# 3V8_Buck_Boost_Converter.net
KiCad netlist of a schematic drawn in Altium Designer
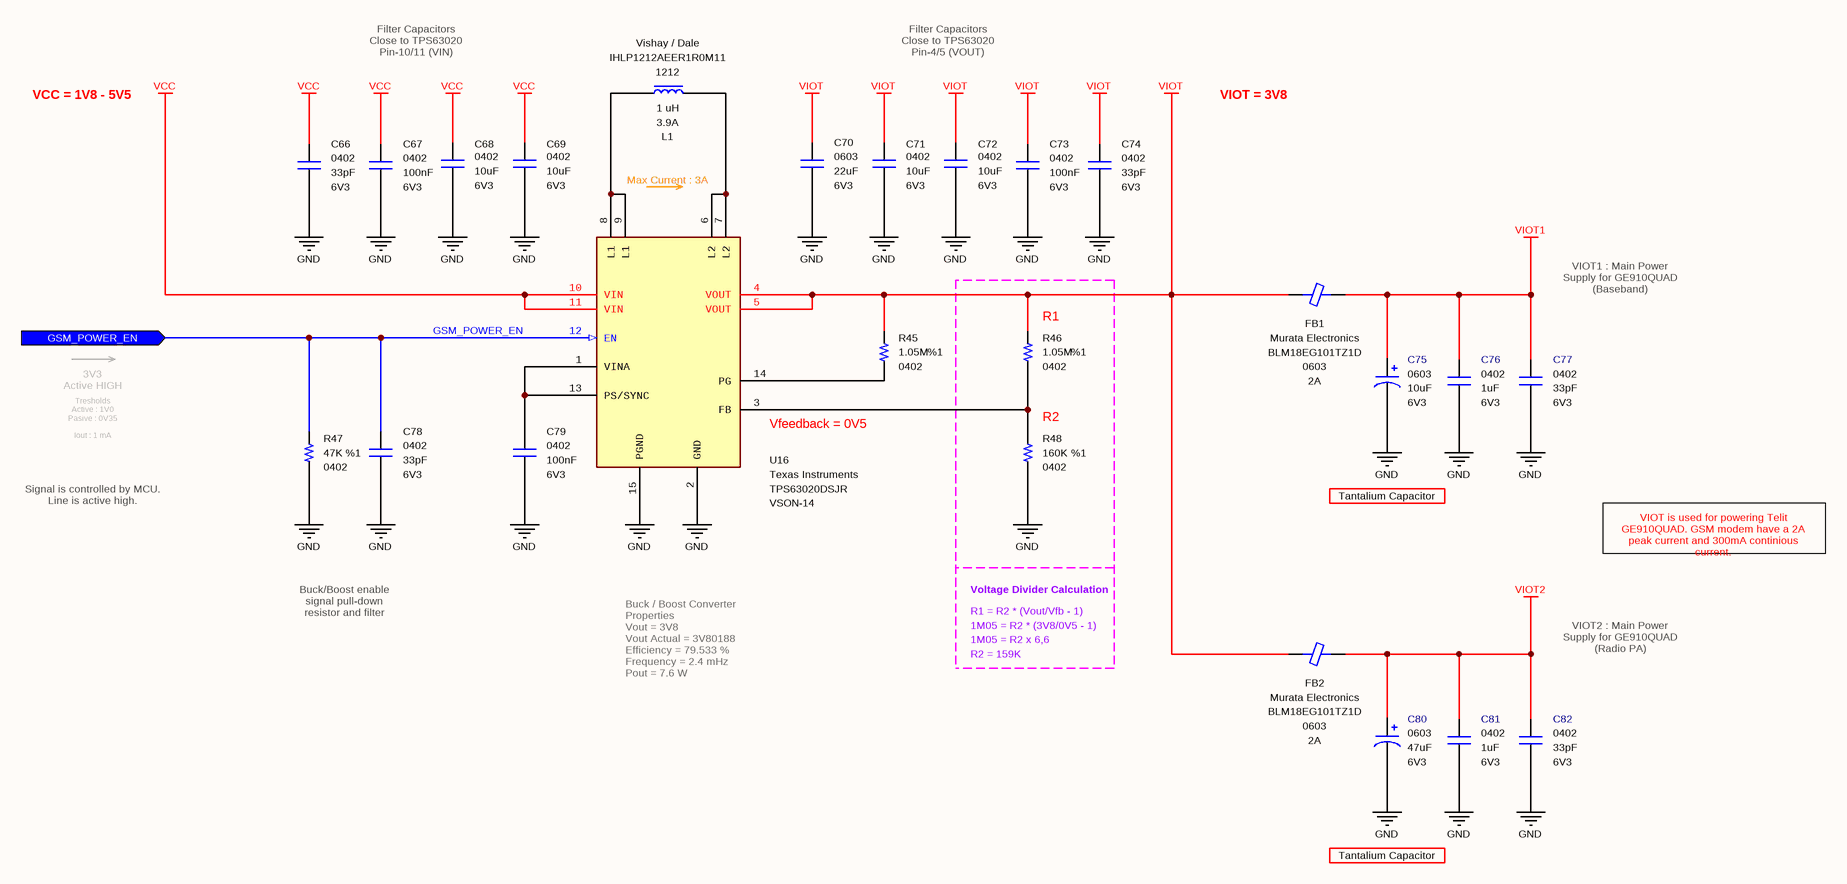
[diagram p0: 3V8 Buck Boost Converter.SchDoc]

(export (version "E")
  (design (tool "Eeschema 10.0.6"))
  (components
    (comp (ref "C66")
      (value "33pF")
      (footprint "CAPACITOR_0402")
      (description "Capacitor - 33pF [0402] (Ceramic)")
      (fields
        (field (name "TOLERANCE") "10%")
        (field (name "CASE") "0402")
        (field (name "VOLTAGE") "6V3")
        (field (name "MANUFACTURER PART NUMBER") "C0402C330J9RACAUTO")
      )
      (libsource (lib "Ovoo_Library") (part "Capacitor - 33pF [0402-6V3]"))
    )
    (comp (ref "C67")
      (value "100nF")
      (footprint "CAPACITOR_0402")
      (description "Capacitor - 100nF [0402-6V3] (Ceramic)")
      (fields
        (field (name "CASE") "0402")
        (field (name "TOLERANCE") "%10")
        (field (name "VOLTAGE") "6V3")
        (field (name "MANUFACTURER PART NUMBER") "04026D104KAT4A")
      )
      (libsource (lib "Ovoo_Library") (part "Capacitor - 100nF [0402-6V3]"))
    )
    (comp (ref "C68")
      (value "10uF")
      (footprint "CAPACITOR_0402")
      (description "Capacitor - 10uF [0402] (Ceramic)")
      (fields
        (field (name "MANUFACTURER PART NUMBER") "C0402C106M9PACTU")
        (field (name "MOUSER PART NUMBER") "80-C0402C106M9P")
        (field (name "CASE") "0402")
        (field (name "VOLTAGE") "6V3")
      )
      (libsource (lib "Ovoo_Library") (part "Capacitor - 10uF [0402-6V3]"))
    )
    (comp (ref "C69")
      (value "10uF")
      (footprint "CAPACITOR_0402")
      (description "Capacitor - 10uF [0402] (Ceramic)")
      (fields
        (field (name "MANUFACTURER PART NUMBER") "C0402C106M9PACTU")
        (field (name "MOUSER PART NUMBER") "80-C0402C106M9P")
        (field (name "CASE") "0402")
        (field (name "VOLTAGE") "6V3")
      )
      (libsource (lib "Ovoo_Library") (part "Capacitor - 10uF [0402-6V3]"))
    )
    (comp (ref "C70")
      (value "22uF")
      (footprint "CAPACITOR_0603")
      (description "Capacitor - 22uF [0603] (Ceramic)")
      (fields
        (field (name "MANUFACTURER PART NUMBER") "GRM188R60J226MEA0D")
        (field (name "TOLERANCE") "%20")
        (field (name "CASE") "0603")
        (field (name "VOLTAGE") "6V3")
      )
      (libsource (lib "Ovoo_Library") (part "Capacitor - 22uF [0603-6V3]"))
    )
    (comp (ref "C71")
      (value "10uF")
      (footprint "CAPACITOR_0402")
      (description "Capacitor - 10uF [0402] (Ceramic)")
      (fields
        (field (name "MANUFACTURER PART NUMBER") "C0402C106M9PACTU")
        (field (name "MOUSER PART NUMBER") "80-C0402C106M9P")
        (field (name "CASE") "0402")
        (field (name "VOLTAGE") "6V3")
      )
      (libsource (lib "Ovoo_Library") (part "Capacitor - 10uF [0402-6V3]"))
    )
    (comp (ref "C72")
      (value "10uF")
      (footprint "CAPACITOR_0402")
      (description "Capacitor - 10uF [0402] (Ceramic)")
      (fields
        (field (name "MANUFACTURER PART NUMBER") "C0402C106M9PACTU")
        (field (name "MOUSER PART NUMBER") "80-C0402C106M9P")
        (field (name "CASE") "0402")
        (field (name "VOLTAGE") "6V3")
      )
      (libsource (lib "Ovoo_Library") (part "Capacitor - 10uF [0402-6V3]"))
    )
    (comp (ref "C73")
      (value "100nF")
      (footprint "CAPACITOR_0402")
      (description "Capacitor - 100nF [0402-6V3] (Ceramic)")
      (fields
        (field (name "CASE") "0402")
        (field (name "TOLERANCE") "%10")
        (field (name "VOLTAGE") "6V3")
        (field (name "MANUFACTURER PART NUMBER") "04026D104KAT4A")
      )
      (libsource (lib "Ovoo_Library") (part "Capacitor - 100nF [0402-6V3]"))
    )
    (comp (ref "C74")
      (value "33pF")
      (footprint "CAPACITOR_0402")
      (description "Capacitor - 33pF [0402] (Ceramic)")
      (fields
        (field (name "TOLERANCE") "10%")
        (field (name "CASE") "0402")
        (field (name "VOLTAGE") "6V3")
        (field (name "MANUFACTURER PART NUMBER") "C0402C330J9RACAUTO")
      )
      (libsource (lib "Ovoo_Library") (part "Capacitor - 33pF [0402-6V3]"))
    )
    (comp (ref "C75")
      (value "10uF")
      (footprint "CAPACITOR_0603 - TANTALUM")
      (description "Capacitor - 10uF [0603] (Tantalium)")
      (fields
        (field (name "TOLERANCE") "20%")
        (field (name "CASE") "0603")
        (field (name "VOLTAGE") "6V3")
        (field (name "MANUFACTURER PART NUMBER") "F380J106MMAAH3")
      )
      (libsource (lib "Ovoo_Library") (part "Capacitor - 10uF [0603-6V3] (Tantalium)"))
    )
    (comp (ref "C76")
      (value "1uF")
      (footprint "CAPACITOR_0402")
      (description "Capacitor - 1uF [0402] (Ceramic)")
      (fields
        (field (name "TOLERANCE") "20%")
        (field (name "CASE") "0402")
        (field (name "VOLTAGE") "6V3")
        (field (name "MANUFACTURER PART NUMBER") "GRM153R60J105ME95D")
      )
      (libsource (lib "Ovoo_Library") (part "Capacitor - 1uF [0402-6V3]"))
    )
    (comp (ref "C77")
      (value "33pF")
      (footprint "CAPACITOR_0402")
      (description "Capacitor - 33pF [0402] (Ceramic)")
      (fields
        (field (name "TOLERANCE") "10%")
        (field (name "CASE") "0402")
        (field (name "VOLTAGE") "6V3")
        (field (name "MANUFACTURER PART NUMBER") "C0402C330J9RACAUTO")
      )
      (libsource (lib "Ovoo_Library") (part "Capacitor - 33pF [0402-6V3]"))
    )
    (comp (ref "C78")
      (value "33pF")
      (footprint "CAPACITOR_0402")
      (description "Capacitor - 33pF [0402] (Ceramic)")
      (fields
        (field (name "TOLERANCE") "10%")
        (field (name "CASE") "0402")
        (field (name "VOLTAGE") "6V3")
        (field (name "MANUFACTURER PART NUMBER") "C0402C330J9RACAUTO")
      )
      (libsource (lib "Ovoo_Library") (part "Capacitor - 33pF [0402-6V3]"))
    )
    (comp (ref "C79")
      (value "100nF")
      (footprint "CAPACITOR_0402")
      (description "Capacitor - 100nF [0402-6V3] (Ceramic)")
      (fields
        (field (name "CASE") "0402")
        (field (name "TOLERANCE") "%10")
        (field (name "VOLTAGE") "6V3")
        (field (name "MANUFACTURER PART NUMBER") "04026D104KAT4A")
      )
      (libsource (lib "Ovoo_Library") (part "Capacitor - 100nF [0402-6V3]"))
    )
    (comp (ref "C80")
      (value "47uF")
      (footprint "CAPACITOR_0603 - TANTALUM")
      (description "Capacitor - 47uF [0603] (Tantalium)")
      (fields
        (field (name "TOLERANCE") "20%")
        (field (name "CASE") "0603")
        (field (name "VOLTAGE") "6V3")
        (field (name "MANUFACTURER PART NUMBER") "F380J476MMAAXEH3")
      )
      (libsource (lib "Ovoo_Library") (part "Capacitor - 47u [0603-6V3] (Tantalium)"))
    )
    (comp (ref "C81")
      (value "1uF")
      (footprint "CAPACITOR_0402")
      (description "Capacitor - 1uF [0402] (Ceramic)")
      (fields
        (field (name "TOLERANCE") "20%")
        (field (name "CASE") "0402")
        (field (name "VOLTAGE") "6V3")
        (field (name "MANUFACTURER PART NUMBER") "GRM153R60J105ME95D")
      )
      (libsource (lib "Ovoo_Library") (part "Capacitor - 1uF [0402-6V3]"))
    )
    (comp (ref "C82")
      (value "33pF")
      (footprint "CAPACITOR_0402")
      (description "Capacitor - 33pF [0402] (Ceramic)")
      (fields
        (field (name "TOLERANCE") "10%")
        (field (name "CASE") "0402")
        (field (name "VOLTAGE") "6V3")
        (field (name "MANUFACTURER PART NUMBER") "C0402C330J9RACAUTO")
      )
      (libsource (lib "Ovoo_Library") (part "Capacitor - 33pF [0402-6V3]"))
    )
    (comp (ref "FB1")
      (value "BLM18EG101TZ1D")
      (footprint "INDUCATOR_0603")
      (description "Ferrite Beads 0603 100ohms 2000mA Auto Infotainment")
      (fields
        (field (name "TOLERANCE") "25%")
        (field (name "CASE") "0603")
        (field (name "MAXIMUM DC CURRENT") "2A")
        (field (name "MOUSER PART NUMBER") "81-BLM18EG101TZ1D")
        (field (name "MANUFACTURER NAME") "Murata Electronics")
      )
      (libsource (lib "Ovoo_Library") (part "Ferrite Bead - 2A [0603]"))
    )
    (comp (ref "FB2")
      (value "BLM18EG101TZ1D")
      (footprint "INDUCATOR_0603")
      (description "Ferrite Beads 0603 100ohms 2000mA Auto Infotainment")
      (fields
        (field (name "TOLERANCE") "25%")
        (field (name "CASE") "0603")
        (field (name "MAXIMUM DC CURRENT") "2A")
        (field (name "MOUSER PART NUMBER") "81-BLM18EG101TZ1D")
        (field (name "MANUFACTURER NAME") "Murata Electronics")
      )
      (libsource (lib "Ovoo_Library") (part "Ferrite Bead - 2A [0603]"))
    )
    (comp (ref "L1")
      (value "1 uH")
      (footprint "IHLP-1212")
      (description "Fixed Inductors 1uH 20%")
      (fields
        (field (name "TOLERANCE") "20%")
        (field (name "MAXIMUM DC CURRENT") "3.9A")
        (field (name "CASE") "1212")
        (field (name "MANUFACTURER PART NUMBER") "IHLP1212AEER1R0M11")
        (field (name "MANUFACTURER NAME") "Vishay / Dale")
        (field (name "Comment") "Vishay - IHLP1212AEER1R0M11")
      )
      (libsource (lib "Ovoo_Library") (part "Inductor - 1 uH [1212]"))
    )
    (comp (ref "R45")
      (value "1.05M")
      (footprint "RESISTOR_0402")
      (description "Thick Film Resistors - SMD 1/16 W 1.05 Mohms 1%")
      (fields
        (field (name "MANUFACTURER PART NUMBER") "CRCW04021M05FKED")
        (field (name "MOUSER PART NUMBER") "71-CRCW04021M05FKED")
        (field (name "TOLERANCE") "%1")
        (field (name "CASE") "0402")
      )
      (libsource (lib "Ovoo_Library") (part "Resistor - 1.05M"))
    )
    (comp (ref "R46")
      (value "1.05M")
      (footprint "RESISTOR_0402")
      (description "Thick Film Resistors - SMD 1/16 W 1.05 Mohms 1%")
      (fields
        (field (name "MANUFACTURER PART NUMBER") "CRCW04021M05FKED")
        (field (name "MOUSER PART NUMBER") "71-CRCW04021M05FKED")
        (field (name "TOLERANCE") "%1")
        (field (name "CASE") "0402")
      )
      (libsource (lib "Ovoo_Library") (part "Resistor - 1.05M"))
    )
    (comp (ref "R47")
      (value "47K")
      (footprint "RESISTOR_0402")
      (description "Thick Film Resistors - SMD 1/16 W 47 Kohms 1%")
      (fields
        (field (name "TOLERANCE") "%1")
        (field (name "CASE") "0402")
        (field (name "MANUFACTURER PART NUMBER") "CRCW040247K0FKED")
        (field (name "Comment") "47K - 0402 - %1 - 1/16W")
      )
      (libsource (lib "Ovoo_Library") (part "Resistor - 47K"))
    )
    (comp (ref "R48")
      (value "160K")
      (footprint "RESISTOR_0402")
      (description "Thick Film Resistors - SMD 1/16 W 159 Kohms 1%")
      (fields
        (field (name "MANUFACTURER PART NUMBER") "CRCW0402160KFKED")
        (field (name "TOLERANCE") "%1")
        (field (name "CASE") "0402")
        (field (name "Comment") "Thick Film Resistor")
      )
      (libsource (lib "Ovoo_Library") (part "Resistor - 160K"))
    )
    (comp (ref "U16")
      (value "Texas Instruments - TPS63020DSJR")
      (footprint "VSON-14")
      (description "Switching Voltage Regulators 93% Eff Buck-Boost Converter")
      (fields
        (field (name "MANUFACTURER PART NUMBER") "TPS63020DSJR")
        (field (name "MANUFACTURER NAME") "Texas Instruments")
        (field (name "CASE") "VSON-14")
      )
      (libsource (lib "Ovoo_Library") (part "IC - TPS63020DSJR"))
    )
  )
  (nets
    (net (code "1") (name "/GSM_POWER_EN") (class "Default")
      (node (ref "C78") (pin "2") (pinfunction "2_2") (pintype "passive"))
      (node (ref "R47") (pin "2") (pinfunction "2_2") (pintype "passive"))
      (node (ref "U16") (pin "12") (pinfunction "EN_12") (pintype "input"))
    )
    (net (code "2") (name "GND") (class "Default")
      (node (ref "C66") (pin "1") (pinfunction "1_1") (pintype "passive"))
      (node (ref "C67") (pin "2") (pinfunction "2_2") (pintype "passive"))
      (node (ref "C68") (pin "1") (pinfunction "1_1") (pintype "passive"))
      (node (ref "C69") (pin "1") (pinfunction "1_1") (pintype "passive"))
      (node (ref "C70") (pin "1") (pinfunction "1_1") (pintype "passive"))
      (node (ref "C71") (pin "1") (pinfunction "1_1") (pintype "passive"))
      (node (ref "C72") (pin "1") (pinfunction "1_1") (pintype "passive"))
      (node (ref "C73") (pin "2") (pinfunction "2_2") (pintype "passive"))
      (node (ref "C74") (pin "1") (pinfunction "1_1") (pintype "passive"))
      (node (ref "C75") (pin "2") (pinfunction "2_2") (pintype "passive"))
      (node (ref "C76") (pin "1") (pinfunction "1_1") (pintype "passive"))
      (node (ref "C77") (pin "1") (pinfunction "1_1") (pintype "passive"))
      (node (ref "C78") (pin "1") (pinfunction "1_1") (pintype "passive"))
      (node (ref "C79") (pin "2") (pinfunction "2_2") (pintype "passive"))
      (node (ref "C80") (pin "2") (pinfunction "2_2") (pintype "passive"))
      (node (ref "C81") (pin "1") (pinfunction "1_1") (pintype "passive"))
      (node (ref "C82") (pin "1") (pinfunction "1_1") (pintype "passive"))
      (node (ref "R47") (pin "1") (pinfunction "1_1") (pintype "passive"))
      (node (ref "R48") (pin "1") (pinfunction "1_1") (pintype "passive"))
      (node (ref "U16") (pin "15") (pinfunction "PGND_15") (pintype "power_in"))
      (node (ref "U16") (pin "2") (pinfunction "GND_2") (pintype "power_in"))
    )
    (net (code "3") (name "Net-(L1-Pad1)") (class "Default")
      (node (ref "L1") (pin "1") (pinfunction "1_1") (pintype "passive"))
      (node (ref "U16") (pin "8") (pinfunction "L1_8") (pintype "passive"))
      (node (ref "U16") (pin "9") (pinfunction "L1_9") (pintype "passive"))
    )
    (net (code "4") (name "Net-(L1-Pad2)") (class "Default")
      (node (ref "L1") (pin "2") (pinfunction "2_2") (pintype "passive"))
      (node (ref "U16") (pin "6") (pinfunction "L2_6") (pintype "passive"))
      (node (ref "U16") (pin "7") (pinfunction "L2_7") (pintype "passive"))
    )
    (net (code "5") (name "Net-(U16-FB)") (class "Default")
      (node (ref "R46") (pin "1") (pinfunction "1_1") (pintype "passive"))
      (node (ref "R48") (pin "2") (pinfunction "2_2") (pintype "passive"))
      (node (ref "U16") (pin "3") (pinfunction "FB_3") (pintype "passive"))
    )
    (net (code "6") (name "Net-(U16-PG)") (class "Default")
      (node (ref "R45") (pin "1") (pinfunction "1_1") (pintype "passive"))
      (node (ref "U16") (pin "14") (pinfunction "PG_14") (pintype "passive"))
    )
    (net (code "7") (name "Net-(U16-PS{slash}SYNC)") (class "Default")
      (node (ref "C79") (pin "1") (pinfunction "1_1") (pintype "passive"))
      (node (ref "U16") (pin "1") (pinfunction "VINA_1") (pintype "passive"))
      (node (ref "U16") (pin "13") (pinfunction "PS/SYNC_13") (pintype "passive"))
    )
    (net (code "8") (name "VCC") (class "Default")
      (node (ref "C66") (pin "2") (pinfunction "2_2") (pintype "passive"))
      (node (ref "C67") (pin "1") (pinfunction "1_1") (pintype "passive"))
      (node (ref "C68") (pin "2") (pinfunction "2_2") (pintype "passive"))
      (node (ref "C69") (pin "2") (pinfunction "2_2") (pintype "passive"))
      (node (ref "U16") (pin "10") (pinfunction "VIN_10") (pintype "power_in"))
      (node (ref "U16") (pin "11") (pinfunction "VIN_11") (pintype "power_in"))
    )
    (net (code "9") (name "VIOT") (class "Default")
      (node (ref "C70") (pin "2") (pinfunction "2_2") (pintype "passive"))
      (node (ref "C71") (pin "2") (pinfunction "2_2") (pintype "passive"))
      (node (ref "C72") (pin "2") (pinfunction "2_2") (pintype "passive"))
      (node (ref "C73") (pin "1") (pinfunction "1_1") (pintype "passive"))
      (node (ref "C74") (pin "2") (pinfunction "2_2") (pintype "passive"))
      (node (ref "FB1") (pin "1") (pinfunction "1_1") (pintype "passive"))
      (node (ref "FB2") (pin "1") (pinfunction "1_1") (pintype "passive"))
      (node (ref "R45") (pin "2") (pinfunction "2_2") (pintype "passive"))
      (node (ref "R46") (pin "2") (pinfunction "2_2") (pintype "passive"))
      (node (ref "U16") (pin "4") (pinfunction "VOUT_4") (pintype "power_in"))
      (node (ref "U16") (pin "5") (pinfunction "VOUT_5") (pintype "power_in"))
    )
    (net (code "10") (name "VIOT1") (class "Default")
      (node (ref "C75") (pin "1") (pinfunction "1_1") (pintype "passive"))
      (node (ref "C76") (pin "2") (pinfunction "2_2") (pintype "passive"))
      (node (ref "C77") (pin "2") (pinfunction "2_2") (pintype "passive"))
      (node (ref "FB1") (pin "2") (pinfunction "2_2") (pintype "passive"))
    )
    (net (code "11") (name "VIOT2") (class "Default")
      (node (ref "C80") (pin "1") (pinfunction "1_1") (pintype "passive"))
      (node (ref "C81") (pin "2") (pinfunction "2_2") (pintype "passive"))
      (node (ref "C82") (pin "2") (pinfunction "2_2") (pintype "passive"))
      (node (ref "FB2") (pin "2") (pinfunction "2_2") (pintype "passive"))
    )
  )
)
